# I2C_UV_Sensor.net
KiCad netlist of a schematic drawn in Altium Designer
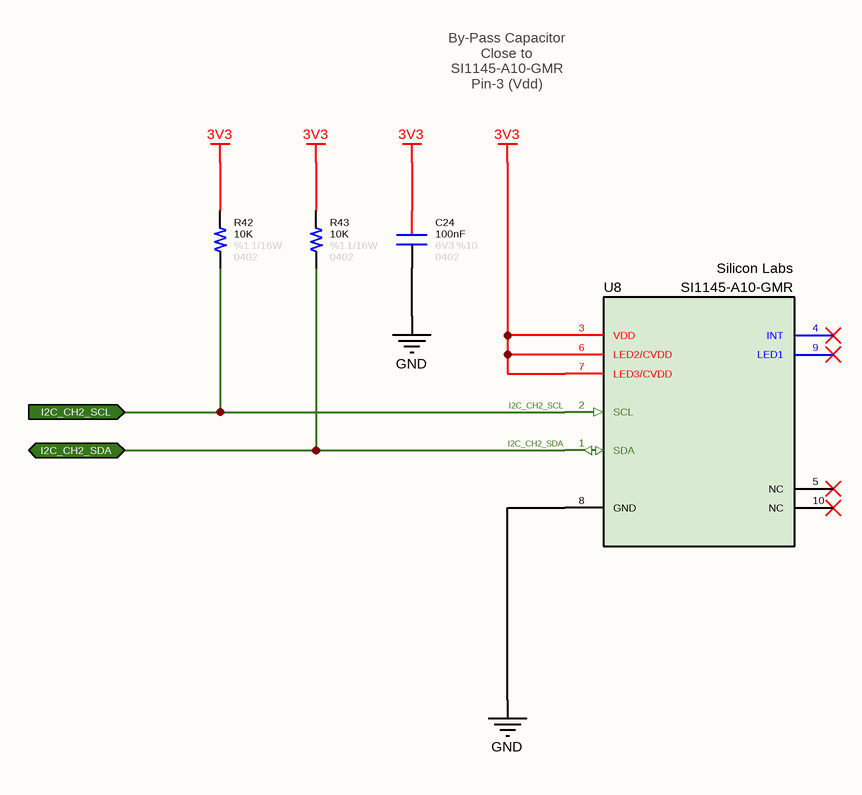
[diagram p0: I2C UV Sensor.SchDoc]

(export (version "E")
  (design (tool "Eeschema 10.0.6"))
  (components
    (comp (ref "C24")
      (value "100nF")
      (footprint "CAPACITOR_0402")
      (description "Capacitor - 100nF [0402-6V3] (Ceramic)")
      (fields
        (field (name "MANUFACTURER PART NUMBER") "04026D104KAT4A")
        (field (name "TOLERANCE") "%10")
        (field (name "VOLTAGE") "6V3")
        (field (name "CASE") "0402")
        (field (name "Comment") "Capacitor - 100nF [0402] (Ceramic)")
      )
      (libsource (lib "Akkoyun") (part "Capacitor - 100nF [0402-6V3]"))
    )
    (comp (ref "R42")
      (value "10K")
      (footprint "RESISTOR_0402")
      (description "Thick Film Resistors - SMD 1/16 W 10 KOhm 1%")
      (fields
        (field (name "MANUFACTURER PART NUMBER") "CRCW040210K0FKED")
        (field (name "TOLERANCE") "%1")
        (field (name "CASE") "0402")
        (field (name "POWER") "1/16W")
        (field (name "Comment") "10K - 0402 - %1 - 1/16W")
      )
      (libsource (lib "Akkoyun") (part "Resistor - 10K [0402]"))
    )
    (comp (ref "R43")
      (value "10K")
      (footprint "RESISTOR_0402")
      (description "Thick Film Resistors - SMD 1/16 W 10 KOhm 1%")
      (fields
        (field (name "MANUFACTURER PART NUMBER") "CRCW040210K0FKED")
        (field (name "TOLERANCE") "%1")
        (field (name "CASE") "0402")
        (field (name "POWER") "1/16W")
        (field (name "Comment") "10K - 0402 - %1 - 1/16W")
      )
      (libsource (lib "Akkoyun") (part "Resistor - 10K [0402]"))
    )
    (comp (ref "U8")
      (value "Si1145-A10-GMR")
      (footprint "SI1145")
      (description "Proximity Sensors I2C UV Index and Proximity/Ambient Light Sensor with 1 LED Driver")
      (fields
        (field (name "MANUFACTURER PART NUMBER") "SI1145-A10-GMR")
        (field (name "MANUFACTURER NAME") "Silicon Labs")
      )
      (libsource (lib "Akkoyun") (part "IC - Si1145-A10-GMR"))
    )
  )
  (nets
    (net (code "1") (name "/I2C_CH2_SCL") (class "Default")
      (node (ref "R42") (pin "1") (pinfunction "1_1") (pintype "passive"))
      (node (ref "U8") (pin "2") (pinfunction "SCL_2") (pintype "input"))
    )
    (net (code "2") (name "/I2C_CH2_SDA") (class "Default")
      (node (ref "R43") (pin "1") (pinfunction "1_1") (pintype "passive"))
      (node (ref "U8") (pin "1") (pinfunction "SDA_1") (pintype "bidirectional"))
    )
    (net (code "3") (name "3V3") (class "Default")
      (node (ref "C24") (pin "2") (pinfunction "2_2") (pintype "passive"))
      (node (ref "R42") (pin "2") (pinfunction "2_2") (pintype "passive"))
      (node (ref "R43") (pin "2") (pinfunction "2_2") (pintype "passive"))
      (node (ref "U8") (pin "3") (pinfunction "VDD_3") (pintype "power_in"))
      (node (ref "U8") (pin "6") (pinfunction "LED2/CVDD_6") (pintype "power_in"))
      (node (ref "U8") (pin "7") (pinfunction "LED3/CVDD_7") (pintype "power_in"))
    )
    (net (code "4") (name "GND") (class "Default")
      (node (ref "C24") (pin "1") (pinfunction "1_1") (pintype "passive"))
      (node (ref "U8") (pin "8") (pinfunction "GND_8") (pintype "power_in"))
    )
    (net (code "5") (name "unconnected-(U8-INT-Pad4)") (class "Default")
      (node (ref "U8") (pin "4") (pinfunction "INT_4") (pintype "passive+no_connect"))
    )
    (net (code "6") (name "unconnected-(U8-LED1-Pad9)") (class "Default")
      (node (ref "U8") (pin "9") (pinfunction "LED1_9") (pintype "passive+no_connect"))
    )
    (net (code "7") (name "unconnected-(U8-NC-Pad5)") (class "Default")
      (node (ref "U8") (pin "5") (pinfunction "NC_5") (pintype "passive+no_connect"))
    )
    (net (code "8") (name "unconnected-(U8-NC-Pad10)") (class "Default")
      (node (ref "U8") (pin "10") (pinfunction "NC_10") (pintype "passive+no_connect"))
    )
  )
)
